# Medusa-AI-coral-dev.net
KiCad netlist of a schematic drawn in Altium Designer
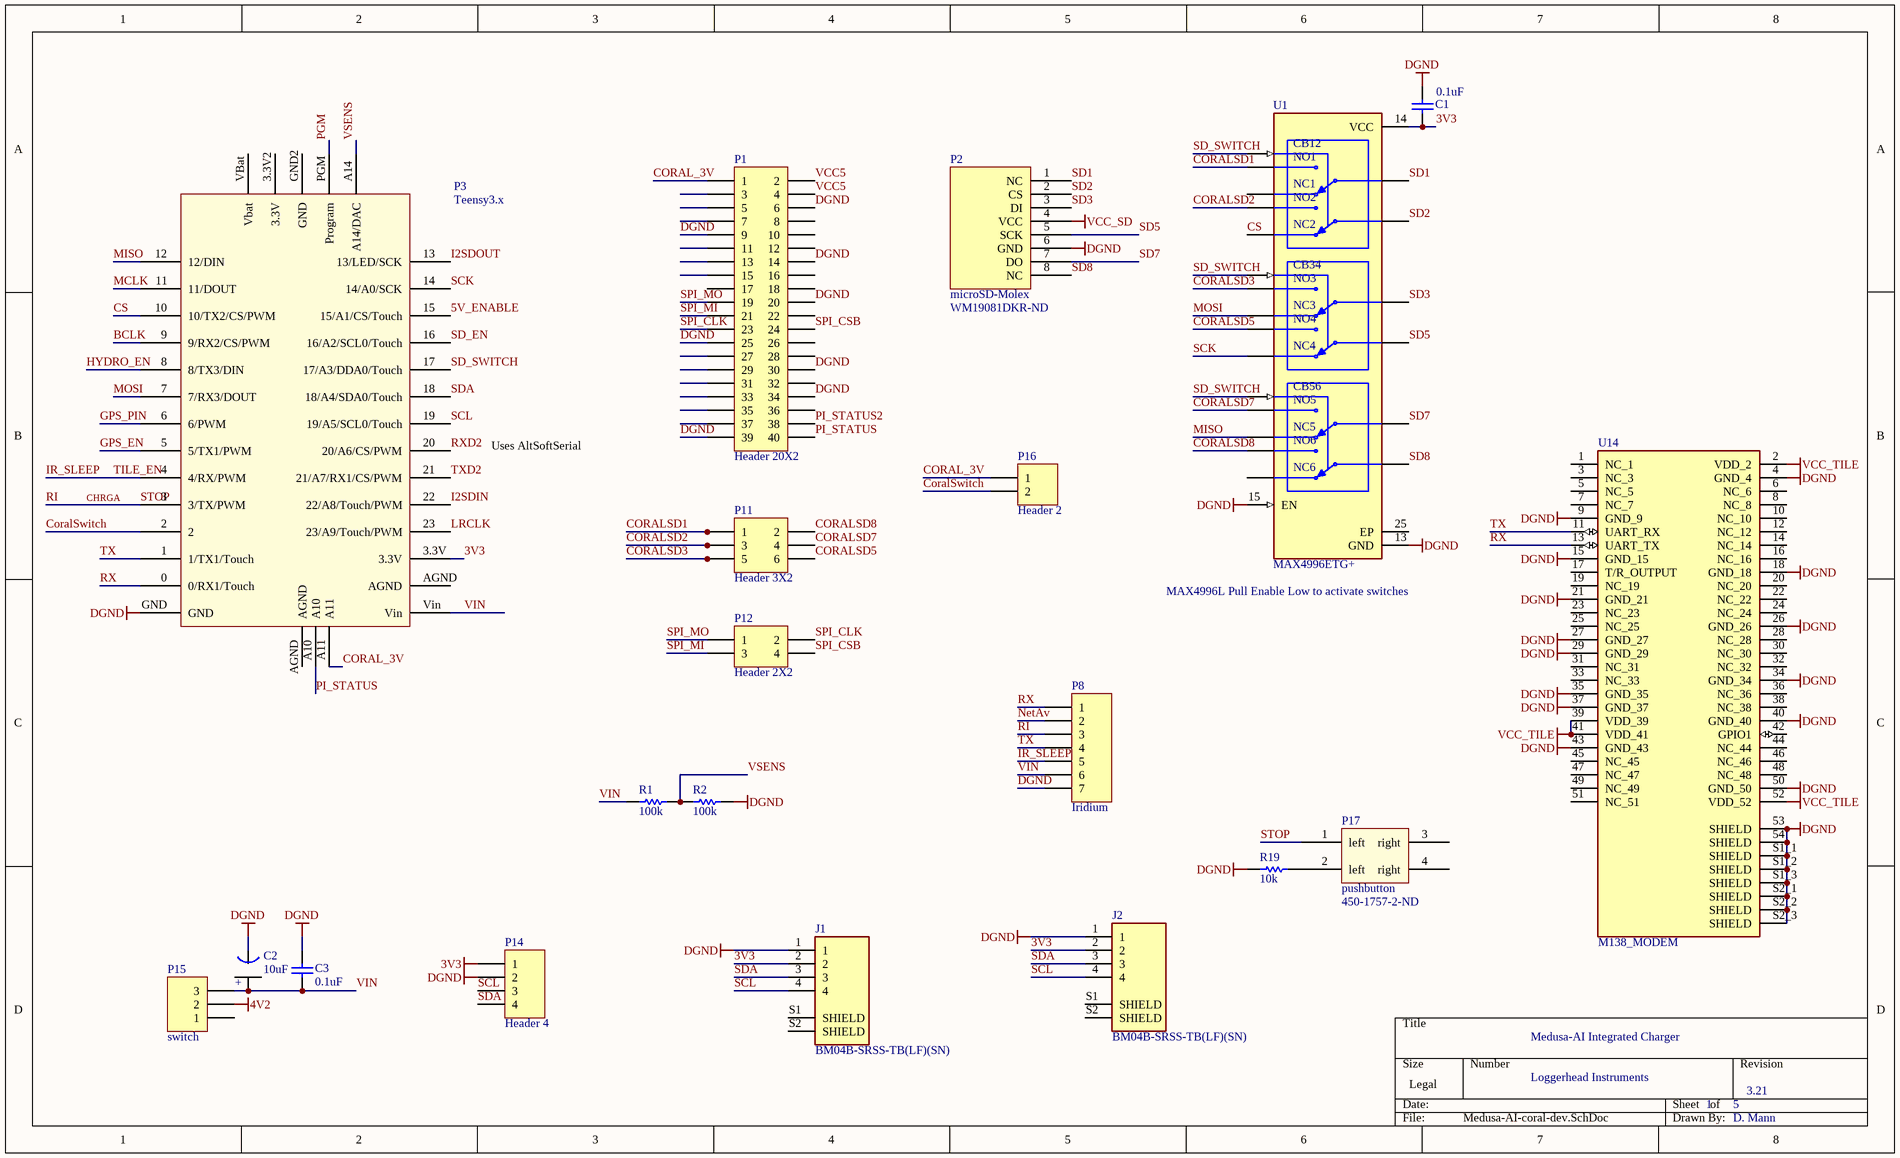
[diagram p0: Medusa-AI-coral-dev.SchDoc]

(export (version "E")
  (design (tool "Eeschema 10.0.6"))
  (components
    (comp (ref "C1")
      (value "0.1uF")
      (footprint "0402")
      (description "Ceramic Chip Capacitor - Standard")
      (fields (field (name "PUBLISHER") "Altium Limited"))
      (libsource (lib "KEMET Chip Capacitor") (part "C0402"))
    )
    (comp (ref "C2") (value "10uF") (footprint "Tant0805") (libsource (lib "Loggerhead") (part "Tant0805")))
    (comp (ref "C3")
      (value "0.1uF")
      (footprint "0402")
      (description "Ceramic Chip Capacitor - Standard")
      (fields (field (name "PUBLISHER") "Altium Limited"))
      (libsource (lib "KEMET Chip Capacitor") (part "C0402"))
    )
    (comp (ref "J1")
      (value "BM04B-SRSS-TB(LF)(SN)")
      (footprint "CONN_BM04B-SRSS-TB(LF)(SN)")
      (description "Connector Header Surface Mount 4 position 0.039 _1.00mm_")
      (fields (field (name "MF") "JST Sales") (field (name "MP") "BM04B-SRSS-TB_LF__SN_"))
      (libsource (lib "BM04B-SRSS-TB_LF__SN_") (part "BM04B-SRSS-TB(LF)(SN)"))
    )
    (comp (ref "J2")
      (value "BM04B-SRSS-TB(LF)(SN)")
      (footprint "CONN_BM04B-SRSS-TB(LF)(SN)")
      (description "Connector Header Surface Mount 4 position 0.039 _1.00mm_")
      (fields (field (name "MF") "JST Sales") (field (name "MP") "BM04B-SRSS-TB_LF__SN_"))
      (libsource (lib "BM04B-SRSS-TB_LF__SN_") (part "BM04B-SRSS-TB(LF)(SN)"))
    )
    (comp (ref "P1")
      (value "Header 20X2")
      (footprint "HDR2X20")
      (description "Header, 20-Pin, Dual row")
      (fields (field (name "PUBLISHER") "Altium Limited"))
      (libsource (lib "Miscellaneous Connectors") (part "Header 20X2"))
    )
    (comp (ref "P2")
      (value "microSD-Molex")
      (footprint "microSD_Molex_hinged")
      (fields (field (name "SUPPLIER PART NUMBER 1") "WM19081DKR-ND"))
      (libsource (lib "Loggerhead") (part "microSD_Molex_hinged"))
    )
    (comp (ref "P3")
      (value "Teensy3.x")
      (footprint "Teensy3.x")
      (libsource (lib "Teensy") (part "Teensy3.x"))
    )
    (comp (ref "P8")
      (value "Iridium")
      (footprint "HDR1X7")
      (description "Header, 7-Pin")
      (fields (field (name "PUBLISHER") "Altium Limited"))
      (libsource (lib "Miscellaneous Connectors") (part "Header 7"))
    )
    (comp (ref "P11")
      (value "Header 3X2")
      (footprint "HDR2X3")
      (description "Header, 3-Pin, Dual row")
      (fields (field (name "PUBLISHER") "Altium Limited"))
      (libsource (lib "Miscellaneous Connectors") (part "Header 3X2"))
    )
    (comp (ref "P12")
      (value "Header 2X2")
      (footprint "HDR2X2")
      (description "Header, 2-Pin, Dual row")
      (fields (field (name "PUBLISHER") "Altium Limited"))
      (libsource (lib "Miscellaneous Connectors") (part "Header 2X2"))
    )
    (comp (ref "P14")
      (value "Header 4")
      (footprint "HDR1X4")
      (description "Header, 4-Pin")
      (fields (field (name "PUBLISHER") "Altium Limited"))
      (libsource (lib "Miscellaneous Connectors") (part "Header 4"))
    )
    (comp (ref "P15")
      (value "switch")
      (footprint "HDR1X3")
      (description "Header, 3-Pin")
      (fields (field (name "PUBLISHER") "Altium Limited"))
      (libsource (lib "Miscellaneous Connectors") (part "Header 3"))
    )
    (comp (ref "P16")
      (value "Header 2")
      (footprint "HDR1X2")
      (description "Header, 2-Pin")
      (fields (field (name "PUBLISHER") "Altium Limited"))
      (libsource (lib "Miscellaneous Connectors") (part "Header 2"))
    )
    (comp (ref "P17")
      (value "pushbutton")
      (footprint "SOP4")
      (fields (field (name "SUPPLIER PART NUMBER 1") "450-1757-2-ND"))
      (libsource (lib "Loggerhead") (part "pushbutton"))
    )
    (comp (ref "R1")
      (value "100k")
      (footprint "3-0603")
      (fields (field (name "PUBLISHER") "Altium Limited"))
      (libsource (lib "Panasonic Resistor") (part "ERJ3RK"))
    )
    (comp (ref "R2")
      (value "100k")
      (footprint "3-0603")
      (fields (field (name "PUBLISHER") "Altium Limited"))
      (libsource (lib "Panasonic Resistor") (part "ERJ3RK"))
    )
    (comp (ref "R19")
      (value "10k")
      (footprint "3-0603")
      (fields (field (name "PUBLISHER") "Altium Limited"))
      (libsource (lib "Panasonic Resistor") (part "ERJ3RK"))
    )
    (comp (ref "U1")
      (value "MAX4996ETG+")
      (footprint "QFN40P350X350X80-25N")
      (description "3 Circuit IC Switch 2:2 4Ohm 24-TQFN (4x4)")
      (fields (field (name "MF") "Maxim Integrated"))
      (libsource (lib "MAX4996ETG_") (part "MAX4996ETG+"))
    )
    (comp (ref "U14")
      (value "M138_MODEM")
      (footprint "XCVR_M138_MODEM")
      (description "Swarm M138 Modem")
      (fields (field (name "MF") "Swarm") (field (name "MP") "M138 Modem"))
      (libsource (lib "M138_MODEM") (part "M138_MODEM"))
    )
  )
  (nets
    (net (code "1") (name "/5V_ENABLE") (class "Default")
      (node (ref "P3") (pin "15") (pinfunction "15/A1/CS/Touch_15") (pintype "passive"))
    )
    (net (code "2") (name "/BCLK") (class "Default")
      (node (ref "P3") (pin "9") (pinfunction "9/RX2/CS/PWM_9") (pintype "passive"))
    )
    (net (code "3") (name "/CHRGA") (class "Default")
      (node (ref "P17") (pin "1") (pinfunction "left_1") (pintype "passive"))
      (node (ref "P3") (pin "3") (pinfunction "3/TX/PWM_3") (pintype "passive"))
      (node (ref "P8") (pin "3") (pinfunction "3_3") (pintype "passive"))
    )
    (net (code "4") (name "/CORALSD1") (class "Default")
      (node (ref "P11") (pin "1") (pinfunction "1_1") (pintype "passive"))
      (node (ref "U1") (pin "19") (pinfunction "NO1_19") (pintype "passive"))
    )
    (net (code "5") (name "/CORALSD2") (class "Default")
      (node (ref "P11") (pin "3") (pinfunction "3_3") (pintype "passive"))
      (node (ref "U1") (pin "20") (pinfunction "NO2_20") (pintype "passive"))
    )
    (net (code "6") (name "/CORALSD3") (class "Default")
      (node (ref "P11") (pin "5") (pinfunction "5_5") (pintype "passive"))
      (node (ref "U1") (pin "21") (pinfunction "NO3_21") (pintype "passive"))
    )
    (net (code "7") (name "/CORALSD5") (class "Default")
      (node (ref "P11") (pin "6") (pinfunction "6_6") (pintype "passive"))
      (node (ref "U1") (pin "22") (pinfunction "NO4_22") (pintype "passive"))
    )
    (net (code "8") (name "/CORALSD7") (class "Default")
      (node (ref "P11") (pin "4") (pinfunction "4_4") (pintype "passive"))
      (node (ref "U1") (pin "23") (pinfunction "NO5_23") (pintype "passive"))
    )
    (net (code "9") (name "/CORALSD8") (class "Default")
      (node (ref "P11") (pin "2") (pinfunction "2_2") (pintype "passive"))
      (node (ref "U1") (pin "24") (pinfunction "NO6_24") (pintype "passive"))
    )
    (net (code "10") (name "/CORAL_3V") (class "Default")
      (node (ref "P1") (pin "1") (pinfunction "1_1") (pintype "passive"))
      (node (ref "P16") (pin "1") (pinfunction "1_1") (pintype "passive"))
      (node (ref "P3") (pin "A11") (pinfunction "A11_A11") (pintype "passive"))
    )
    (net (code "11") (name "/CS") (class "Default")
      (node (ref "P3") (pin "10") (pinfunction "10/TX2/CS/PWM_10") (pintype "passive"))
      (node (ref "U1") (pin "11") (pinfunction "NC2_11") (pintype "passive"))
    )
    (net (code "12") (name "/CoralSwitch") (class "Default")
      (node (ref "P16") (pin "2") (pinfunction "2_2") (pintype "passive"))
      (node (ref "P3") (pin "2") (pinfunction "2_2") (pintype "passive"))
    )
    (net (code "13") (name "/GPS_EN") (class "Default")
      (node (ref "P3") (pin "5") (pinfunction "5/TX1/PWM_5") (pintype "passive"))
    )
    (net (code "14") (name "/GPS_PIN") (class "Default")
      (node (ref "P3") (pin "6") (pinfunction "6/PWM_6") (pintype "passive"))
    )
    (net (code "15") (name "/HYDRO_EN") (class "Default")
      (node (ref "P3") (pin "8") (pinfunction "8/TX3/DIN_8") (pintype "passive"))
    )
    (net (code "16") (name "/I2SDIN") (class "Default")
      (node (ref "P3") (pin "22") (pinfunction "22/A8/Touch/PWM_22") (pintype "passive"))
    )
    (net (code "17") (name "/I2SDOUT") (class "Default")
      (node (ref "P3") (pin "13") (pinfunction "13/LED/SCK_13") (pintype "passive"))
    )
    (net (code "18") (name "/IR_SLEEP") (class "Default")
      (node (ref "P3") (pin "4") (pinfunction "4/RX/PWM_4") (pintype "passive"))
      (node (ref "P8") (pin "5") (pinfunction "5_5") (pintype "passive"))
    )
    (net (code "19") (name "/LRCLK") (class "Default")
      (node (ref "P3") (pin "23") (pinfunction "23/A9/Touch/PWM_23") (pintype "passive"))
    )
    (net (code "20") (name "/MCLK") (class "Default")
      (node (ref "P3") (pin "11") (pinfunction "11/DOUT_11") (pintype "passive"))
    )
    (net (code "21") (name "/MISO") (class "Default")
      (node (ref "P3") (pin "12") (pinfunction "12/DIN_12") (pintype "passive"))
      (node (ref "U1") (pin "8") (pinfunction "NC5_8") (pintype "passive"))
    )
    (net (code "22") (name "/MOSI") (class "Default")
      (node (ref "P3") (pin "7") (pinfunction "7/RX3/DOUT_7") (pintype "passive"))
      (node (ref "U1") (pin "10") (pinfunction "NC3_10") (pintype "passive"))
    )
    (net (code "23") (name "/NetAv") (class "Default")
      (node (ref "P8") (pin "2") (pinfunction "2_2") (pintype "passive"))
    )
    (net (code "24") (name "/PGM") (class "Default")
      (node (ref "P3") (pin "PGM") (pinfunction "Program_PGM") (pintype "passive"))
    )
    (net (code "25") (name "/PI_STATUS") (class "Default")
      (node (ref "P1") (pin "40") (pinfunction "40_40") (pintype "passive"))
      (node (ref "P3") (pin "A10") (pinfunction "A10_A10") (pintype "passive"))
    )
    (net (code "26") (name "/PI_STATUS2") (class "Default")
      (node (ref "P1") (pin "38") (pinfunction "38_38") (pintype "passive"))
    )
    (net (code "27") (name "/RX") (class "Default")
      (node (ref "P3") (pin "0") (pinfunction "0/RX1/Touch_0") (pintype "passive"))
      (node (ref "P8") (pin "1") (pinfunction "1_1") (pintype "passive"))
      (node (ref "U14") (pin "13") (pinfunction "UART_TX_13") (pintype "bidirectional"))
    )
    (net (code "28") (name "/RXD2") (class "Default")
      (node (ref "P3") (pin "20") (pinfunction "20/A6/CS/PWM_20") (pintype "passive"))
    )
    (net (code "29") (name "/SCK") (class "Default")
      (node (ref "P3") (pin "14") (pinfunction "14/A0/SCK_14") (pintype "passive"))
      (node (ref "U1") (pin "9") (pinfunction "NC4_9") (pintype "passive"))
    )
    (net (code "30") (name "/SCL") (class "Default")
      (node (ref "J1") (pin "4") (pinfunction "4_4") (pintype "passive"))
      (node (ref "J2") (pin "4") (pinfunction "4_4") (pintype "passive"))
      (node (ref "P14") (pin "3") (pinfunction "3_3") (pintype "passive"))
      (node (ref "P3") (pin "19") (pinfunction "19/A5/SCL0/Touch_19") (pintype "passive"))
    )
    (net (code "31") (name "/SD1") (class "Default")
      (node (ref "P2") (pin "1") (pinfunction "NC_1") (pintype "passive"))
      (node (ref "U1") (pin "18") (pinfunction "COM1_18") (pintype "passive"))
    )
    (net (code "32") (name "/SD2") (class "Default")
      (node (ref "P2") (pin "2") (pinfunction "CS_2") (pintype "passive"))
      (node (ref "U1") (pin "17") (pinfunction "COM2_17") (pintype "passive"))
    )
    (net (code "33") (name "/SD3") (class "Default")
      (node (ref "P2") (pin "3") (pinfunction "DI_3") (pintype "passive"))
      (node (ref "U1") (pin "16") (pinfunction "COM3_16") (pintype "passive"))
    )
    (net (code "34") (name "/SD5") (class "Default")
      (node (ref "P2") (pin "5") (pinfunction "SCK_5") (pintype "passive"))
      (node (ref "U1") (pin "4") (pinfunction "COM4_4") (pintype "passive"))
    )
    (net (code "35") (name "/SD7") (class "Default")
      (node (ref "P2") (pin "7") (pinfunction "DO_7") (pintype "passive"))
      (node (ref "U1") (pin "5") (pinfunction "COM5_5") (pintype "passive"))
    )
    (net (code "36") (name "/SD8") (class "Default")
      (node (ref "P2") (pin "8") (pinfunction "NC_8") (pintype "passive"))
      (node (ref "U1") (pin "6") (pinfunction "COM6_6") (pintype "passive"))
    )
    (net (code "37") (name "/SDA") (class "Default")
      (node (ref "J1") (pin "3") (pinfunction "3_3") (pintype "passive"))
      (node (ref "J2") (pin "3") (pinfunction "3_3") (pintype "passive"))
      (node (ref "P14") (pin "4") (pinfunction "4_4") (pintype "passive"))
      (node (ref "P3") (pin "18") (pinfunction "18/A4/SDA0/Touch_18") (pintype "passive"))
    )
    (net (code "38") (name "/SD_EN") (class "Default")
      (node (ref "P3") (pin "16") (pinfunction "16/A2/SCL0/Touch_16") (pintype "passive"))
    )
    (net (code "39") (name "/SD_SWITCH") (class "Default")
      (node (ref "P3") (pin "17") (pinfunction "17/A3/DDA0/Touch_17") (pintype "passive"))
      (node (ref "U1") (pin "1") (pinfunction "CB12_1") (pintype "input"))
      (node (ref "U1") (pin "2") (pinfunction "CB34_2") (pintype "input"))
      (node (ref "U1") (pin "3") (pinfunction "CB56_3") (pintype "input"))
    )
    (net (code "40") (name "/SPI_CLK") (class "Default")
      (node (ref "P1") (pin "23") (pinfunction "23_23") (pintype "passive"))
      (node (ref "P12") (pin "2") (pinfunction "2_2") (pintype "passive"))
    )
    (net (code "41") (name "/SPI_CSB") (class "Default")
      (node (ref "P1") (pin "24") (pinfunction "24_24") (pintype "passive"))
      (node (ref "P12") (pin "4") (pinfunction "4_4") (pintype "passive"))
    )
    (net (code "42") (name "/SPI_MI") (class "Default")
      (node (ref "P1") (pin "21") (pinfunction "21_21") (pintype "passive"))
      (node (ref "P12") (pin "3") (pinfunction "3_3") (pintype "passive"))
    )
    (net (code "43") (name "/SPI_MO") (class "Default")
      (node (ref "P1") (pin "19") (pinfunction "19_19") (pintype "passive"))
      (node (ref "P12") (pin "1") (pinfunction "1_1") (pintype "passive"))
    )
    (net (code "44") (name "/TX") (class "Default")
      (node (ref "P3") (pin "1") (pinfunction "1/TX1/Touch_1") (pintype "passive"))
      (node (ref "P8") (pin "4") (pinfunction "4_4") (pintype "passive"))
      (node (ref "U14") (pin "11") (pinfunction "UART_RX_11") (pintype "bidirectional"))
    )
    (net (code "45") (name "/TXD2") (class "Default")
      (node (ref "P3") (pin "21") (pinfunction "21/A7/RX1/CS/PWM_21") (pintype "passive"))
    )
    (net (code "46") (name "/VCC5") (class "Default")
      (node (ref "P1") (pin "2") (pinfunction "2_2") (pintype "passive"))
      (node (ref "P1") (pin "4") (pinfunction "4_4") (pintype "passive"))
    )
    (net (code "47") (name "/VIN") (class "Default")
      (node (ref "C2") (pin "2") (pinfunction "+_2") (pintype "passive"))
      (node (ref "C3") (pin "1") (pinfunction "1_1") (pintype "passive"))
      (node (ref "P15") (pin "3") (pinfunction "3_3") (pintype "passive"))
      (node (ref "P3") (pin "Vin") (pinfunction "Vin_Vin") (pintype "passive"))
      (node (ref "P8") (pin "6") (pinfunction "6_6") (pintype "passive"))
      (node (ref "R1") (pin "2") (pinfunction "2_2") (pintype "passive"))
    )
    (net (code "48") (name "/VSENS") (class "Default")
      (node (ref "P3") (pin "A14") (pinfunction "A14/DAC_A14") (pintype "passive"))
      (node (ref "R1") (pin "1") (pinfunction "1_1") (pintype "passive"))
      (node (ref "R2") (pin "2") (pinfunction "2_2") (pintype "passive"))
    )
    (net (code "49") (name "3V3") (class "Default")
      (node (ref "C1") (pin "1") (pinfunction "1_1") (pintype "passive"))
      (node (ref "J1") (pin "2") (pinfunction "2_2") (pintype "passive"))
      (node (ref "J2") (pin "2") (pinfunction "2_2") (pintype "passive"))
      (node (ref "P14") (pin "1") (pinfunction "1_1") (pintype "passive"))
      (node (ref "P3") (pin "3.3V") (pinfunction "3.3V_3.3V") (pintype "passive"))
      (node (ref "U1") (pin "14") (pinfunction "VCC_14") (pintype "power_in"))
    )
    (net (code "50") (name "4V2") (class "Default")
      (node (ref "P15") (pin "2") (pinfunction "2_2") (pintype "passive"))
    )
    (net (code "51") (name "DGND") (class "Default")
      (node (ref "C1") (pin "2") (pinfunction "2_2") (pintype "passive"))
      (node (ref "C2") (pin "1") (pinfunction "GND_1") (pintype "passive"))
      (node (ref "C3") (pin "2") (pinfunction "2_2") (pintype "passive"))
      (node (ref "J1") (pin "1") (pinfunction "1_1") (pintype "passive"))
      (node (ref "J2") (pin "1") (pinfunction "1_1") (pintype "passive"))
      (node (ref "P1") (pin "14") (pinfunction "14_14") (pintype "passive"))
      (node (ref "P1") (pin "20") (pinfunction "20_20") (pintype "passive"))
      (node (ref "P1") (pin "25") (pinfunction "25_25") (pintype "passive"))
      (node (ref "P1") (pin "30") (pinfunction "30_30") (pintype "passive"))
      (node (ref "P1") (pin "34") (pinfunction "34_34") (pintype "passive"))
      (node (ref "P1") (pin "39") (pinfunction "39_39") (pintype "passive"))
      (node (ref "P1") (pin "6") (pinfunction "6_6") (pintype "passive"))
      (node (ref "P1") (pin "9") (pinfunction "9_9") (pintype "passive"))
      (node (ref "P14") (pin "2") (pinfunction "2_2") (pintype "passive"))
      (node (ref "P2") (pin "6") (pinfunction "GND_6") (pintype "passive"))
      (node (ref "P3") (pin "GND") (pinfunction "GND_GND") (pintype "passive"))
      (node (ref "P8") (pin "7") (pinfunction "7_7") (pintype "passive"))
      (node (ref "R19") (pin "2") (pinfunction "2_2") (pintype "passive"))
      (node (ref "R2") (pin "1") (pinfunction "1_1") (pintype "passive"))
      (node (ref "U1") (pin "13") (pinfunction "GND_13") (pintype "power_in"))
      (node (ref "U1") (pin "15") (pinfunction "EN_15") (pintype "input"))
      (node (ref "U14") (pin "15") (pinfunction "GND_15_15") (pintype "power_in"))
      (node (ref "U14") (pin "18") (pinfunction "GND_18_18") (pintype "power_in"))
      (node (ref "U14") (pin "21") (pinfunction "GND_21_21") (pintype "power_in"))
      (node (ref "U14") (pin "26") (pinfunction "GND_26_26") (pintype "power_in"))
      (node (ref "U14") (pin "27") (pinfunction "GND_27_27") (pintype "power_in"))
      (node (ref "U14") (pin "29") (pinfunction "GND_29_29") (pintype "power_in"))
      (node (ref "U14") (pin "34") (pinfunction "GND_34_34") (pintype "power_in"))
      (node (ref "U14") (pin "35") (pinfunction "GND_35_35") (pintype "power_in"))
      (node (ref "U14") (pin "37") (pinfunction "GND_37_37") (pintype "power_in"))
      (node (ref "U14") (pin "4") (pinfunction "GND_4_4") (pintype "power_in"))
      (node (ref "U14") (pin "40") (pinfunction "GND_40_40") (pintype "power_in"))
      (node (ref "U14") (pin "43") (pinfunction "GND_43_43") (pintype "power_in"))
      (node (ref "U14") (pin "50") (pinfunction "GND_50_50") (pintype "power_in"))
      (node (ref "U14") (pin "53") (pinfunction "SHIELD_53") (pintype "passive"))
      (node (ref "U14") (pin "54") (pinfunction "SHIELD_54") (pintype "passive"))
      (node (ref "U14") (pin "9") (pinfunction "GND_9_9") (pintype "power_in"))
      (node (ref "U14") (pin "S1_1") (pinfunction "SHIELD_S1_1") (pintype "passive"))
      (node (ref "U14") (pin "S1_2") (pinfunction "SHIELD_S1_2") (pintype "passive"))
      (node (ref "U14") (pin "S1_3") (pinfunction "SHIELD_S1_3") (pintype "passive"))
      (node (ref "U14") (pin "S2_1") (pinfunction "SHIELD_S2_1") (pintype "passive"))
      (node (ref "U14") (pin "S2_2") (pinfunction "SHIELD_S2_2") (pintype "passive"))
      (node (ref "U14") (pin "S2_3") (pinfunction "SHIELD_S2_3") (pintype "passive"))
    )
    (net (code "52") (name "Net-(P17-left-Pad2)") (class "Default")
      (node (ref "P17") (pin "2") (pinfunction "left_2") (pintype "passive"))
      (node (ref "R19") (pin "1") (pinfunction "1_1") (pintype "passive"))
    )
    (net (code "53") (name "VCC_SD") (class "Default")
      (node (ref "P2") (pin "4") (pinfunction "VCC_4") (pintype "passive"))
    )
    (net (code "54") (name "VCC_TILE") (class "Default")
      (node (ref "U14") (pin "2") (pinfunction "VDD_2_2") (pintype "power_in"))
      (node (ref "U14") (pin "39") (pinfunction "VDD_39_39") (pintype "power_in"))
      (node (ref "U14") (pin "41") (pinfunction "VDD_41_41") (pintype "power_in"))
      (node (ref "U14") (pin "52") (pinfunction "VDD_52_52") (pintype "power_in"))
    )
    (net (code "55") (name "unconnected-(J1-SHIELD-PadS1)") (class "Default")
      (node (ref "J1") (pin "S1") (pinfunction "SHIELD_S1") (pintype "passive"))
    )
    (net (code "56") (name "unconnected-(J1-SHIELD-PadS2)") (class "Default")
      (node (ref "J1") (pin "S2") (pinfunction "SHIELD_S2") (pintype "passive"))
    )
    (net (code "57") (name "unconnected-(J2-SHIELD-PadS1)") (class "Default")
      (node (ref "J2") (pin "S1") (pinfunction "SHIELD_S1") (pintype "passive"))
    )
    (net (code "58") (name "unconnected-(J2-SHIELD-PadS2)") (class "Default")
      (node (ref "J2") (pin "S2") (pinfunction "SHIELD_S2") (pintype "passive"))
    )
    (net (code "59") (name "unconnected-(P1-Pad3)") (class "Default")
      (node (ref "P1") (pin "3") (pinfunction "3_3") (pintype "passive"))
    )
    (net (code "60") (name "unconnected-(P1-Pad5)") (class "Default")
      (node (ref "P1") (pin "5") (pinfunction "5_5") (pintype "passive"))
    )
    (net (code "61") (name "unconnected-(P1-Pad7)") (class "Default")
      (node (ref "P1") (pin "7") (pinfunction "7_7") (pintype "passive"))
    )
    (net (code "62") (name "unconnected-(P1-Pad8)") (class "Default")
      (node (ref "P1") (pin "8") (pinfunction "8_8") (pintype "passive"))
    )
    (net (code "63") (name "unconnected-(P1-Pad10)") (class "Default")
      (node (ref "P1") (pin "10") (pinfunction "10_10") (pintype "passive"))
    )
    (net (code "64") (name "unconnected-(P1-Pad11)") (class "Default")
      (node (ref "P1") (pin "11") (pinfunction "11_11") (pintype "passive"))
    )
    (net (code "65") (name "unconnected-(P1-Pad12)") (class "Default")
      (node (ref "P1") (pin "12") (pinfunction "12_12") (pintype "passive"))
    )
    (net (code "66") (name "unconnected-(P1-Pad13)") (class "Default")
      (node (ref "P1") (pin "13") (pinfunction "13_13") (pintype "passive"))
    )
    (net (code "67") (name "unconnected-(P1-Pad15)") (class "Default")
      (node (ref "P1") (pin "15") (pinfunction "15_15") (pintype "passive"))
    )
    (net (code "68") (name "unconnected-(P1-Pad16)") (class "Default")
      (node (ref "P1") (pin "16") (pinfunction "16_16") (pintype "passive"))
    )
    (net (code "69") (name "unconnected-(P1-Pad17)") (class "Default")
      (node (ref "P1") (pin "17") (pinfunction "17_17") (pintype "passive"))
    )
    (net (code "70") (name "unconnected-(P1-Pad18)") (class "Default")
      (node (ref "P1") (pin "18") (pinfunction "18_18") (pintype "passive"))
    )
    (net (code "71") (name "unconnected-(P1-Pad22)") (class "Default")
      (node (ref "P1") (pin "22") (pinfunction "22_22") (pintype "passive"))
    )
    (net (code "72") (name "unconnected-(P1-Pad26)") (class "Default")
      (node (ref "P1") (pin "26") (pinfunction "26_26") (pintype "passive"))
    )
    (net (code "73") (name "unconnected-(P1-Pad27)") (class "Default")
      (node (ref "P1") (pin "27") (pinfunction "27_27") (pintype "passive"))
    )
    (net (code "74") (name "unconnected-(P1-Pad28)") (class "Default")
      (node (ref "P1") (pin "28") (pinfunction "28_28") (pintype "passive"))
    )
    (net (code "75") (name "unconnected-(P1-Pad29)") (class "Default")
      (node (ref "P1") (pin "29") (pinfunction "29_29") (pintype "passive"))
    )
    (net (code "76") (name "unconnected-(P1-Pad31)") (class "Default")
      (node (ref "P1") (pin "31") (pinfunction "31_31") (pintype "passive"))
    )
    (net (code "77") (name "unconnected-(P1-Pad32)") (class "Default")
      (node (ref "P1") (pin "32") (pinfunction "32_32") (pintype "passive"))
    )
    (net (code "78") (name "unconnected-(P1-Pad33)") (class "Default")
      (node (ref "P1") (pin "33") (pinfunction "33_33") (pintype "passive"))
    )
    (net (code "79") (name "unconnected-(P1-Pad35)") (class "Default")
      (node (ref "P1") (pin "35") (pinfunction "35_35") (pintype "passive"))
    )
    (net (code "80") (name "unconnected-(P1-Pad36)") (class "Default")
      (node (ref "P1") (pin "36") (pinfunction "36_36") (pintype "passive"))
    )
    (net (code "81") (name "unconnected-(P1-Pad37)") (class "Default")
      (node (ref "P1") (pin "37") (pinfunction "37_37") (pintype "passive"))
    )
    (net (code "82") (name "unconnected-(P3-3.3V-Pad3.3V2)") (class "Default")
      (node (ref "P3") (pin "3.3V2") (pinfunction "3.3V_3.3V2") (pintype "passive"))
    )
    (net (code "83") (name "unconnected-(P3-GND-PadGND2)") (class "Default")
      (node (ref "P3") (pin "GND2") (pinfunction "GND_GND2") (pintype "passive"))
    )
    (net (code "84") (name "unconnected-(P3-PadAGND)") (class "Default")
      (node (ref "P3") (pin "AGND") (pinfunction "AGND_AGND") (pintype "passive"))
    )
    (net (code "85") (name "unconnected-(P3-PadAGND)_1") (class "Default")
      (node (ref "P3") (pin "AGND") (pinfunction "AGND_AGND") (pintype "passive"))
    )
    (net (code "86") (name "unconnected-(P3-Vbat-PadVBat)") (class "Default")
      (node (ref "P3") (pin "VBat") (pinfunction "Vbat_VBat") (pintype "passive"))
    )
    (net (code "87") (name "unconnected-(P15-Pad1)") (class "Default")
      (node (ref "P15") (pin "1") (pinfunction "1_1") (pintype "passive"))
    )
    (net (code "88") (name "unconnected-(P17-right-Pad3)") (class "Default")
      (node (ref "P17") (pin "3") (pinfunction "right_3") (pintype "passive"))
    )
    (net (code "89") (name "unconnected-(P17-right-Pad4)") (class "Default")
      (node (ref "P17") (pin "4") (pinfunction "right_4") (pintype "passive"))
    )
    (net (code "90") (name "unconnected-(U1-EP-Pad25)") (class "Default")
      (node (ref "U1") (pin "25") (pinfunction "EP_25") (pintype "power_in"))
    )
    (net (code "91") (name "unconnected-(U1-NC1-Pad12)") (class "Default")
      (node (ref "U1") (pin "12") (pinfunction "NC1_12") (pintype "passive"))
    )
    (net (code "92") (name "unconnected-(U1-NC6-Pad7)") (class "Default")
      (node (ref "U1") (pin "7") (pinfunction "NC6_7") (pintype "passive"))
    )
    (net (code "93") (name "unconnected-(U14-GPIO1-Pad42)") (class "Default")
      (node (ref "U14") (pin "42") (pinfunction "GPIO1_42") (pintype "bidirectional"))
    )
    (net (code "94") (name "unconnected-(U14-NC_1-Pad1)") (class "Default")
      (node (ref "U14") (pin "1") (pinfunction "NC_1_1") (pintype "passive"))
    )
    (net (code "95") (name "unconnected-(U14-NC_3-Pad3)") (class "Default")
      (node (ref "U14") (pin "3") (pinfunction "NC_3_3") (pintype "passive"))
    )
    (net (code "96") (name "unconnected-(U14-NC_5-Pad5)") (class "Default")
      (node (ref "U14") (pin "5") (pinfunction "NC_5_5") (pintype "passive"))
    )
    (net (code "97") (name "unconnected-(U14-NC_6-Pad6)") (class "Default")
      (node (ref "U14") (pin "6") (pinfunction "NC_6_6") (pintype "passive"))
    )
    (net (code "98") (name "unconnected-(U14-NC_7-Pad7)") (class "Default")
      (node (ref "U14") (pin "7") (pinfunction "NC_7_7") (pintype "passive"))
    )
    (net (code "99") (name "unconnected-(U14-NC_8-Pad8)") (class "Default")
      (node (ref "U14") (pin "8") (pinfunction "NC_8_8") (pintype "passive"))
    )
    (net (code "100") (name "unconnected-(U14-NC_10-Pad10)") (class "Default")
      (node (ref "U14") (pin "10") (pinfunction "NC_10_10") (pintype "passive"))
    )
    (net (code "101") (name "unconnected-(U14-NC_12-Pad12)") (class "Default")
      (node (ref "U14") (pin "12") (pinfunction "NC_12_12") (pintype "passive"))
    )
    (net (code "102") (name "unconnected-(U14-NC_14-Pad14)") (class "Default")
      (node (ref "U14") (pin "14") (pinfunction "NC_14_14") (pintype "passive"))
    )
    (net (code "103") (name "unconnected-(U14-NC_16-Pad16)") (class "Default")
      (node (ref "U14") (pin "16") (pinfunction "NC_16_16") (pintype "passive"))
    )
    (net (code "104") (name "unconnected-(U14-NC_19-Pad19)") (class "Default")
      (node (ref "U14") (pin "19") (pinfunction "NC_19_19") (pintype "passive"))
    )
    (net (code "105") (name "unconnected-(U14-NC_20-Pad20)") (class "Default")
      (node (ref "U14") (pin "20") (pinfunction "NC_20_20") (pintype "passive"))
    )
    (net (code "106") (name "unconnected-(U14-NC_22-Pad22)") (class "Default")
      (node (ref "U14") (pin "22") (pinfunction "NC_22_22") (pintype "passive"))
    )
    (net (code "107") (name "unconnected-(U14-NC_23-Pad23)") (class "Default")
      (node (ref "U14") (pin "23") (pinfunction "NC_23_23") (pintype "passive"))
    )
    (net (code "108") (name "unconnected-(U14-NC_24-Pad24)") (class "Default")
      (node (ref "U14") (pin "24") (pinfunction "NC_24_24") (pintype "passive"))
    )
    (net (code "109") (name "unconnected-(U14-NC_25-Pad25)") (class "Default")
      (node (ref "U14") (pin "25") (pinfunction "NC_25_25") (pintype "passive"))
    )
    (net (code "110") (name "unconnected-(U14-NC_28-Pad28)") (class "Default")
      (node (ref "U14") (pin "28") (pinfunction "NC_28_28") (pintype "passive"))
    )
    (net (code "111") (name "unconnected-(U14-NC_30-Pad30)") (class "Default")
      (node (ref "U14") (pin "30") (pinfunction "NC_30_30") (pintype "passive"))
    )
    (net (code "112") (name "unconnected-(U14-NC_31-Pad31)") (class "Default")
      (node (ref "U14") (pin "31") (pinfunction "NC_31_31") (pintype "passive"))
    )
    (net (code "113") (name "unconnected-(U14-NC_32-Pad32)") (class "Default")
      (node (ref "U14") (pin "32") (pinfunction "NC_32_32") (pintype "passive"))
    )
    (net (code "114") (name "unconnected-(U14-NC_33-Pad33)") (class "Default")
      (node (ref "U14") (pin "33") (pinfunction "NC_33_33") (pintype "passive"))
    )
    (net (code "115") (name "unconnected-(U14-NC_36-Pad36)") (class "Default")
      (node (ref "U14") (pin "36") (pinfunction "NC_36_36") (pintype "passive"))
    )
    (net (code "116") (name "unconnected-(U14-NC_38-Pad38)") (class "Default")
      (node (ref "U14") (pin "38") (pinfunction "NC_38_38") (pintype "passive"))
    )
    (net (code "117") (name "unconnected-(U14-NC_44-Pad44)") (class "Default")
      (node (ref "U14") (pin "44") (pinfunction "NC_44_44") (pintype "passive"))
    )
    (net (code "118") (name "unconnected-(U14-NC_45-Pad45)") (class "Default")
      (node (ref "U14") (pin "45") (pinfunction "NC_45_45") (pintype "passive"))
    )
    (net (code "119") (name "unconnected-(U14-NC_46-Pad46)") (class "Default")
      (node (ref "U14") (pin "46") (pinfunction "NC_46_46") (pintype "passive"))
    )
    (net (code "120") (name "unconnected-(U14-NC_47-Pad47)") (class "Default")
      (node (ref "U14") (pin "47") (pinfunction "NC_47_47") (pintype "passive"))
    )
    (net (code "121") (name "unconnected-(U14-NC_48-Pad48)") (class "Default")
      (node (ref "U14") (pin "48") (pinfunction "NC_48_48") (pintype "passive"))
    )
    (net (code "122") (name "unconnected-(U14-NC_49-Pad49)") (class "Default")
      (node (ref "U14") (pin "49") (pinfunction "NC_49_49") (pintype "passive"))
    )
    (net (code "123") (name "unconnected-(U14-NC_51-Pad51)") (class "Default")
      (node (ref "U14") (pin "51") (pinfunction "NC_51_51") (pintype "passive"))
    )
    (net (code "124") (name "unconnected-(U14-T{slash}R_OUTPUT-Pad17)") (class "Default")
      (node (ref "U14") (pin "17") (pinfunction "T/R_OUTPUT_17") (pintype "passive"))
    )
  )
)
